# 05_-_BOTOES_LEDS.net
KiCad netlist of a schematic drawn in Altium Designer
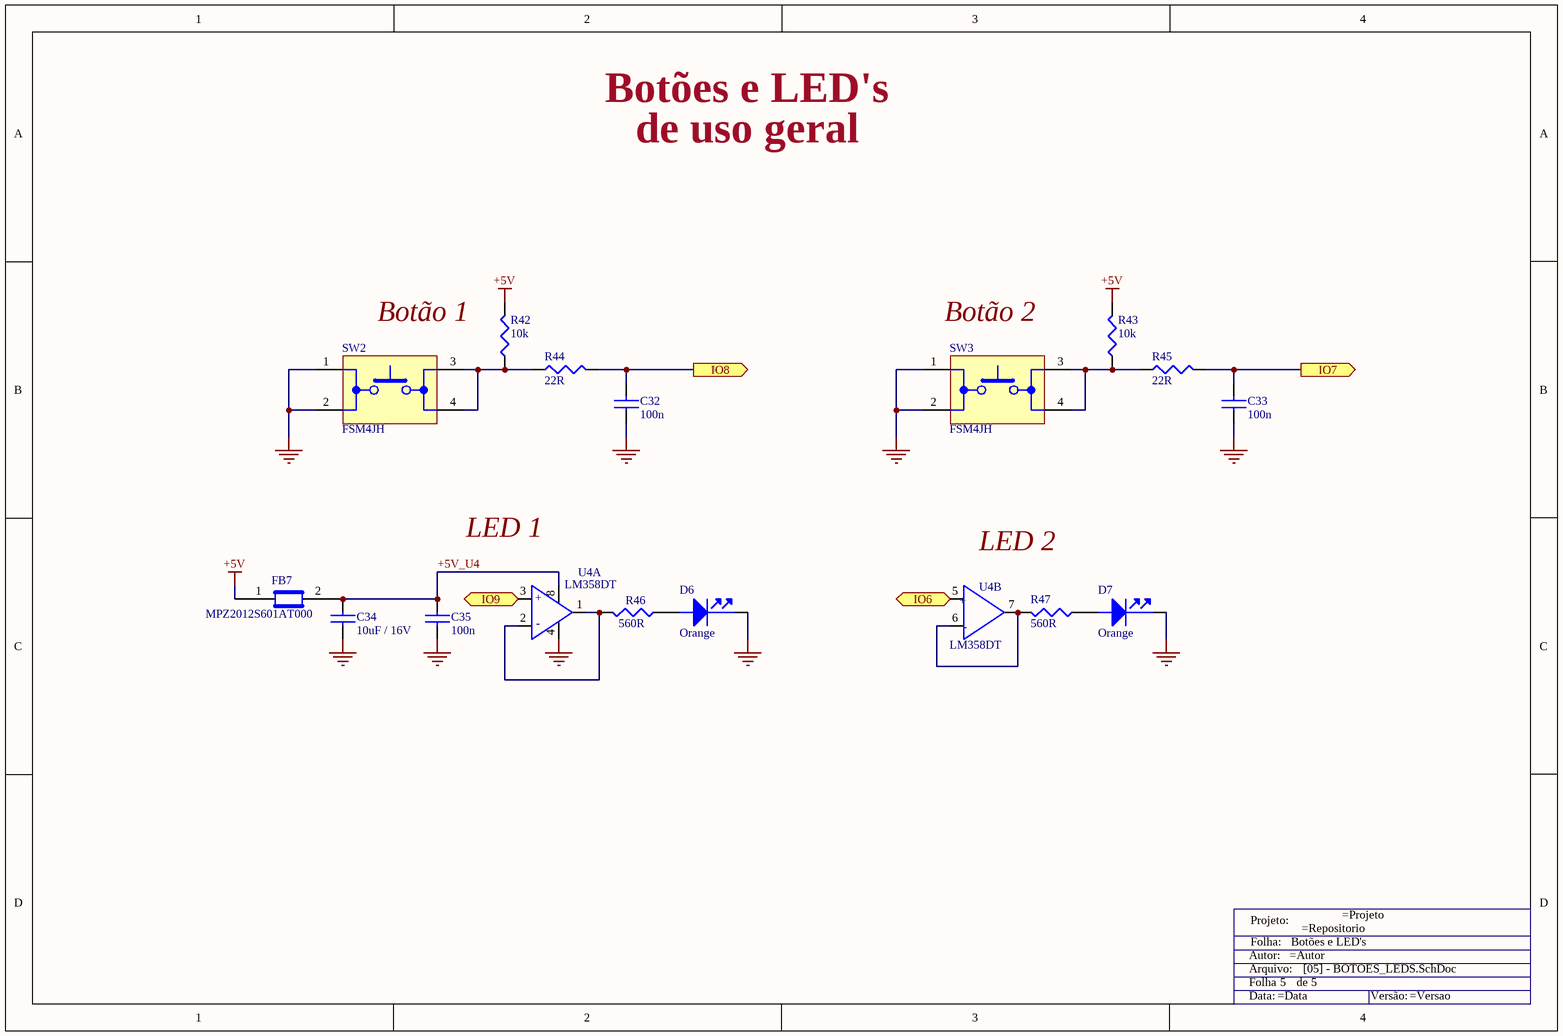
[diagram p0: [05] - BOTOES_LEDS.SchDoc]

(export (version "E")
  (design (tool "Eeschema 10.0.6"))
  (components
    (comp (ref "C32")
      (value "100n")
      (footprint "C0805")
      (description "CAP CER 0.1UF 50V X7R 0805")
      (fields
        (field (name "MANUFACTURER") "TDK Corporation")
        (field (name "MANUFACTURER PART NUMBER") "C2012X7R1H104K085AA")
      )
      (libsource (lib "Servo_Control_Lib") (part "C2012X7R1H104K085AA_1"))
    )
    (comp (ref "C33")
      (value "100n")
      (footprint "C0805")
      (description "CAP CER 0.1UF 50V X7R 0805")
      (fields
        (field (name "MANUFACTURER") "TDK Corporation")
        (field (name "MANUFACTURER PART NUMBER") "C2012X7R1H104K085AA")
      )
      (libsource (lib "Servo_Control_Lib") (part "C2012X7R1H104K085AA_1"))
    )
    (comp (ref "C34")
      (value "10uF / 16V")
      (footprint "C0805")
      (description "CAP CER 10UF 16V X5R 0805")
      (fields
        (field (name "MANUFACTURER") "TDK Corporation")
        (field (name "MANUFACTURER PART NUMBER") "C2012X5R1C106M125AC")
      )
      (libsource (lib "Servo_Control_Lib") (part "C2012X5R1C106M125AC"))
    )
    (comp (ref "C35")
      (value "100n")
      (footprint "C0805")
      (description "CAP CER 0.1UF 50V X7R 0805")
      (fields
        (field (name "MANUFACTURER") "TDK Corporation")
        (field (name "MANUFACTURER PART NUMBER") "C2012X7R1H104K085AA")
      )
      (libsource (lib "Servo_Control_Lib") (part "C2012X7R1H104K085AA_1"))
    )
    (comp (ref "D6")
      (value "Orange")
      (footprint "LED_0603")
      (description "LED ORANGE DIFFUSED 0603 SMD")
      (fields
        (field (name "MANUFACTURER") "OSRAM Opto Semiconductors Inc.")
        (field (name "MANUFACTURER PART NUMBER") "LO L29K-H2K1-24-Z")
      )
      (libsource (lib "Servo_Control_Lib") (part "LO L29K-H2K1-24-Z"))
    )
    (comp (ref "D7")
      (value "Orange")
      (footprint "LED_0603")
      (description "LED ORANGE DIFFUSED 0603 SMD")
      (fields
        (field (name "MANUFACTURER") "OSRAM Opto Semiconductors Inc.")
        (field (name "MANUFACTURER PART NUMBER") "LO L29K-H2K1-24-Z")
      )
      (libsource (lib "Servo_Control_Lib") (part "LO L29K-H2K1-24-Z"))
    )
    (comp (ref "FB7")
      (value "MPZ2012S601AT000")
      (footprint "C0805")
      (description "FERRITE CHIP BEAD 600 OHM SMD")
      (fields (field (name "MANUFACTURER") "TDK Corporation"))
      (libsource (lib "Servo_Control_Lib") (part "MPZ2012S601AT000"))
    )
    (comp (ref "R42")
      (value "10k")
      (footprint "R0805")
      (description "RES SMD 10K OHM 1% 1/8W 0805")
      (fields
        (field (name "MANUFACTURER") "Yageo")
        (field (name "MANUFACTURER PART NUMBER") "RC0805FR-0710KL")
      )
      (libsource (lib "Servo_Control_Lib") (part "RC0805FR-0710KL"))
    )
    (comp (ref "R43")
      (value "10k")
      (footprint "R0805")
      (description "RES SMD 10K OHM 1% 1/8W 0805")
      (fields
        (field (name "MANUFACTURER") "Yageo")
        (field (name "MANUFACTURER PART NUMBER") "RC0805FR-0710KL")
      )
      (libsource (lib "Servo_Control_Lib") (part "RC0805FR-0710KL"))
    )
    (comp (ref "R44")
      (value "22R")
      (footprint "R0805")
      (description "RES SMD 22 OHM 1% 1/8W 0805")
      (fields
        (field (name "MANUFACTURER") "Yageo")
        (field (name "MANUFACTURER PART NUMBER") "RC0805FR-0722RL")
      )
      (libsource (lib "Servo_Control_Lib") (part "RC0805FR-0722RL"))
    )
    (comp (ref "R45")
      (value "22R")
      (footprint "R0805")
      (description "RES SMD 22 OHM 1% 1/8W 0805")
      (fields
        (field (name "MANUFACTURER") "Yageo")
        (field (name "MANUFACTURER PART NUMBER") "RC0805FR-0722RL")
      )
      (libsource (lib "Servo_Control_Lib") (part "RC0805FR-0722RL"))
    )
    (comp (ref "R46")
      (value "560R")
      (footprint "R0805")
      (description "RES SMD 560 OHM 1% 1/8W 0805")
      (fields
        (field (name "MANUFACTURER") "Yageo")
        (field (name "MANUFACTURER PART NUMBER") "RC0805FR-07560RL")
      )
      (libsource (lib "Servo_Control_Lib") (part "RC0805FR-07560RL"))
    )
    (comp (ref "R47")
      (value "560R")
      (footprint "R0805")
      (description "RES SMD 560 OHM 1% 1/8W 0805")
      (fields
        (field (name "MANUFACTURER") "Yageo")
        (field (name "MANUFACTURER PART NUMBER") "RC0805FR-07560RL")
      )
      (libsource (lib "Servo_Control_Lib") (part "RC0805FR-07560RL"))
    )
    (comp (ref "SW2")
      (value "FSM4JH")
      (footprint "FSM4JH")
      (description "Tactile Switches SPST OFF-(ON) Round pushbutton")
      (fields (field (name "MANUFACTURER") "TE Connectivity / Alcoswitch"))
      (libsource (lib "Servo_Control_Lib") (part "FSM4JH"))
    )
    (comp (ref "SW3")
      (value "FSM4JH")
      (footprint "FSM4JH")
      (description "Tactile Switches SPST OFF-(ON) Round pushbutton")
      (fields (field (name "MANUFACTURER") "TE Connectivity / Alcoswitch"))
      (libsource (lib "Servo_Control_Lib") (part "FSM4JH"))
    )
    (comp (ref "TitleBlock5")
      (value "Title Block")
      (libsource (lib "Servo_Control_Lib") (part "Title Block"))
    )
    (comp (ref "U4")
      (value "LM358DT")
      (footprint "SO-8")
      (description "Operational Amplifiers - Op Amps Dual Low Power")
      (fields (field (name "MANUFACTURER") "STMicroelectronics"))
      (libsource (lib "Servo_Control_Lib") (part "LM358DT"))
    )
  )
  (nets
    (net (code "1") (name "+5V") (class "Default")
      (node (ref "FB7") (pin "1") (pinfunction "1_1") (pintype "passive"))
      (node (ref "R42") (pin "2") (pinfunction "2_2") (pintype "passive"))
      (node (ref "R43") (pin "2") (pinfunction "2_2") (pintype "passive"))
    )
    (net (code "2") (name "/+5V_U4") (class "Default")
      (node (ref "C34") (pin "1") (pinfunction "1_1") (pintype "passive"))
      (node (ref "C35") (pin "1") (pinfunction "1_1") (pintype "passive"))
      (node (ref "FB7") (pin "2") (pinfunction "2_2") (pintype "passive"))
      (node (ref "U4") (pin "8") (pinfunction "VCC_8") (pintype "passive"))
    )
    (net (code "3") (name "/IO6") (class "Default")
      (node (ref "U4") (pin "5") (pinfunction "IN2+_5") (pintype "passive"))
    )
    (net (code "4") (name "/IO7") (class "Default")
      (node (ref "C33") (pin "2") (pinfunction "2_2") (pintype "passive"))
      (node (ref "R45") (pin "2") (pinfunction "2_2") (pintype "passive"))
    )
    (net (code "5") (name "/IO8") (class "Default")
      (node (ref "C32") (pin "2") (pinfunction "2_2") (pintype "passive"))
      (node (ref "R44") (pin "2") (pinfunction "2_2") (pintype "passive"))
    )
    (net (code "6") (name "/IO9") (class "Default")
      (node (ref "U4") (pin "3") (pinfunction "IN1+_3") (pintype "passive"))
    )
    (net (code "7") (name "GND") (class "Default")
      (node (ref "C32") (pin "1") (pinfunction "1_1") (pintype "passive"))
      (node (ref "C33") (pin "1") (pinfunction "1_1") (pintype "passive"))
      (node (ref "C34") (pin "2") (pinfunction "2_2") (pintype "passive"))
      (node (ref "C35") (pin "2") (pinfunction "2_2") (pintype "passive"))
      (node (ref "D6") (pin "1") (pinfunction "Cathode_1") (pintype "passive"))
      (node (ref "D7") (pin "1") (pinfunction "Cathode_1") (pintype "passive"))
      (node (ref "SW2") (pin "1") (pinfunction "1_1") (pintype "passive"))
      (node (ref "SW2") (pin "2") (pinfunction "2_2") (pintype "passive"))
      (node (ref "SW3") (pin "1") (pinfunction "1_1") (pintype "passive"))
      (node (ref "SW3") (pin "2") (pinfunction "2_2") (pintype "passive"))
      (node (ref "U4") (pin "4") (pinfunction "GND_4") (pintype "passive"))
    )
    (net (code "8") (name "Net-(D6-Anode)") (class "Default")
      (node (ref "D6") (pin "2") (pinfunction "Anode_2") (pintype "passive"))
      (node (ref "R46") (pin "1") (pinfunction "1_1") (pintype "passive"))
    )
    (net (code "9") (name "Net-(D7-Anode)") (class "Default")
      (node (ref "D7") (pin "2") (pinfunction "Anode_2") (pintype "passive"))
      (node (ref "R47") (pin "1") (pinfunction "1_1") (pintype "passive"))
    )
    (net (code "10") (name "Net-(R42-Pad1)") (class "Default")
      (node (ref "R42") (pin "1") (pinfunction "1_1") (pintype "passive"))
      (node (ref "R44") (pin "1") (pinfunction "1_1") (pintype "passive"))
      (node (ref "SW2") (pin "3") (pinfunction "3_3") (pintype "passive"))
      (node (ref "SW2") (pin "4") (pinfunction "4_4") (pintype "passive"))
    )
    (net (code "11") (name "Net-(R43-Pad1)") (class "Default")
      (node (ref "R43") (pin "1") (pinfunction "1_1") (pintype "passive"))
      (node (ref "R45") (pin "1") (pinfunction "1_1") (pintype "passive"))
      (node (ref "SW3") (pin "3") (pinfunction "3_3") (pintype "passive"))
      (node (ref "SW3") (pin "4") (pinfunction "4_4") (pintype "passive"))
    )
    (net (code "12") (name "Net-(U4A-IN1-)") (class "Default")
      (node (ref "R46") (pin "2") (pinfunction "2_2") (pintype "passive"))
      (node (ref "U4") (pin "1") (pinfunction "OUT1_1") (pintype "passive"))
      (node (ref "U4") (pin "2") (pinfunction "IN1-_2") (pintype "passive"))
    )
    (net (code "13") (name "Net-(U4B-IN2-)") (class "Default")
      (node (ref "R47") (pin "2") (pinfunction "2_2") (pintype "passive"))
      (node (ref "U4") (pin "6") (pinfunction "IN2-_6") (pintype "passive"))
      (node (ref "U4") (pin "7") (pinfunction "OUT2_7") (pintype "passive"))
    )
  )
)
